# Mainboard_Encoder_Interface.net
KiCad netlist of a schematic drawn in Altium Designer
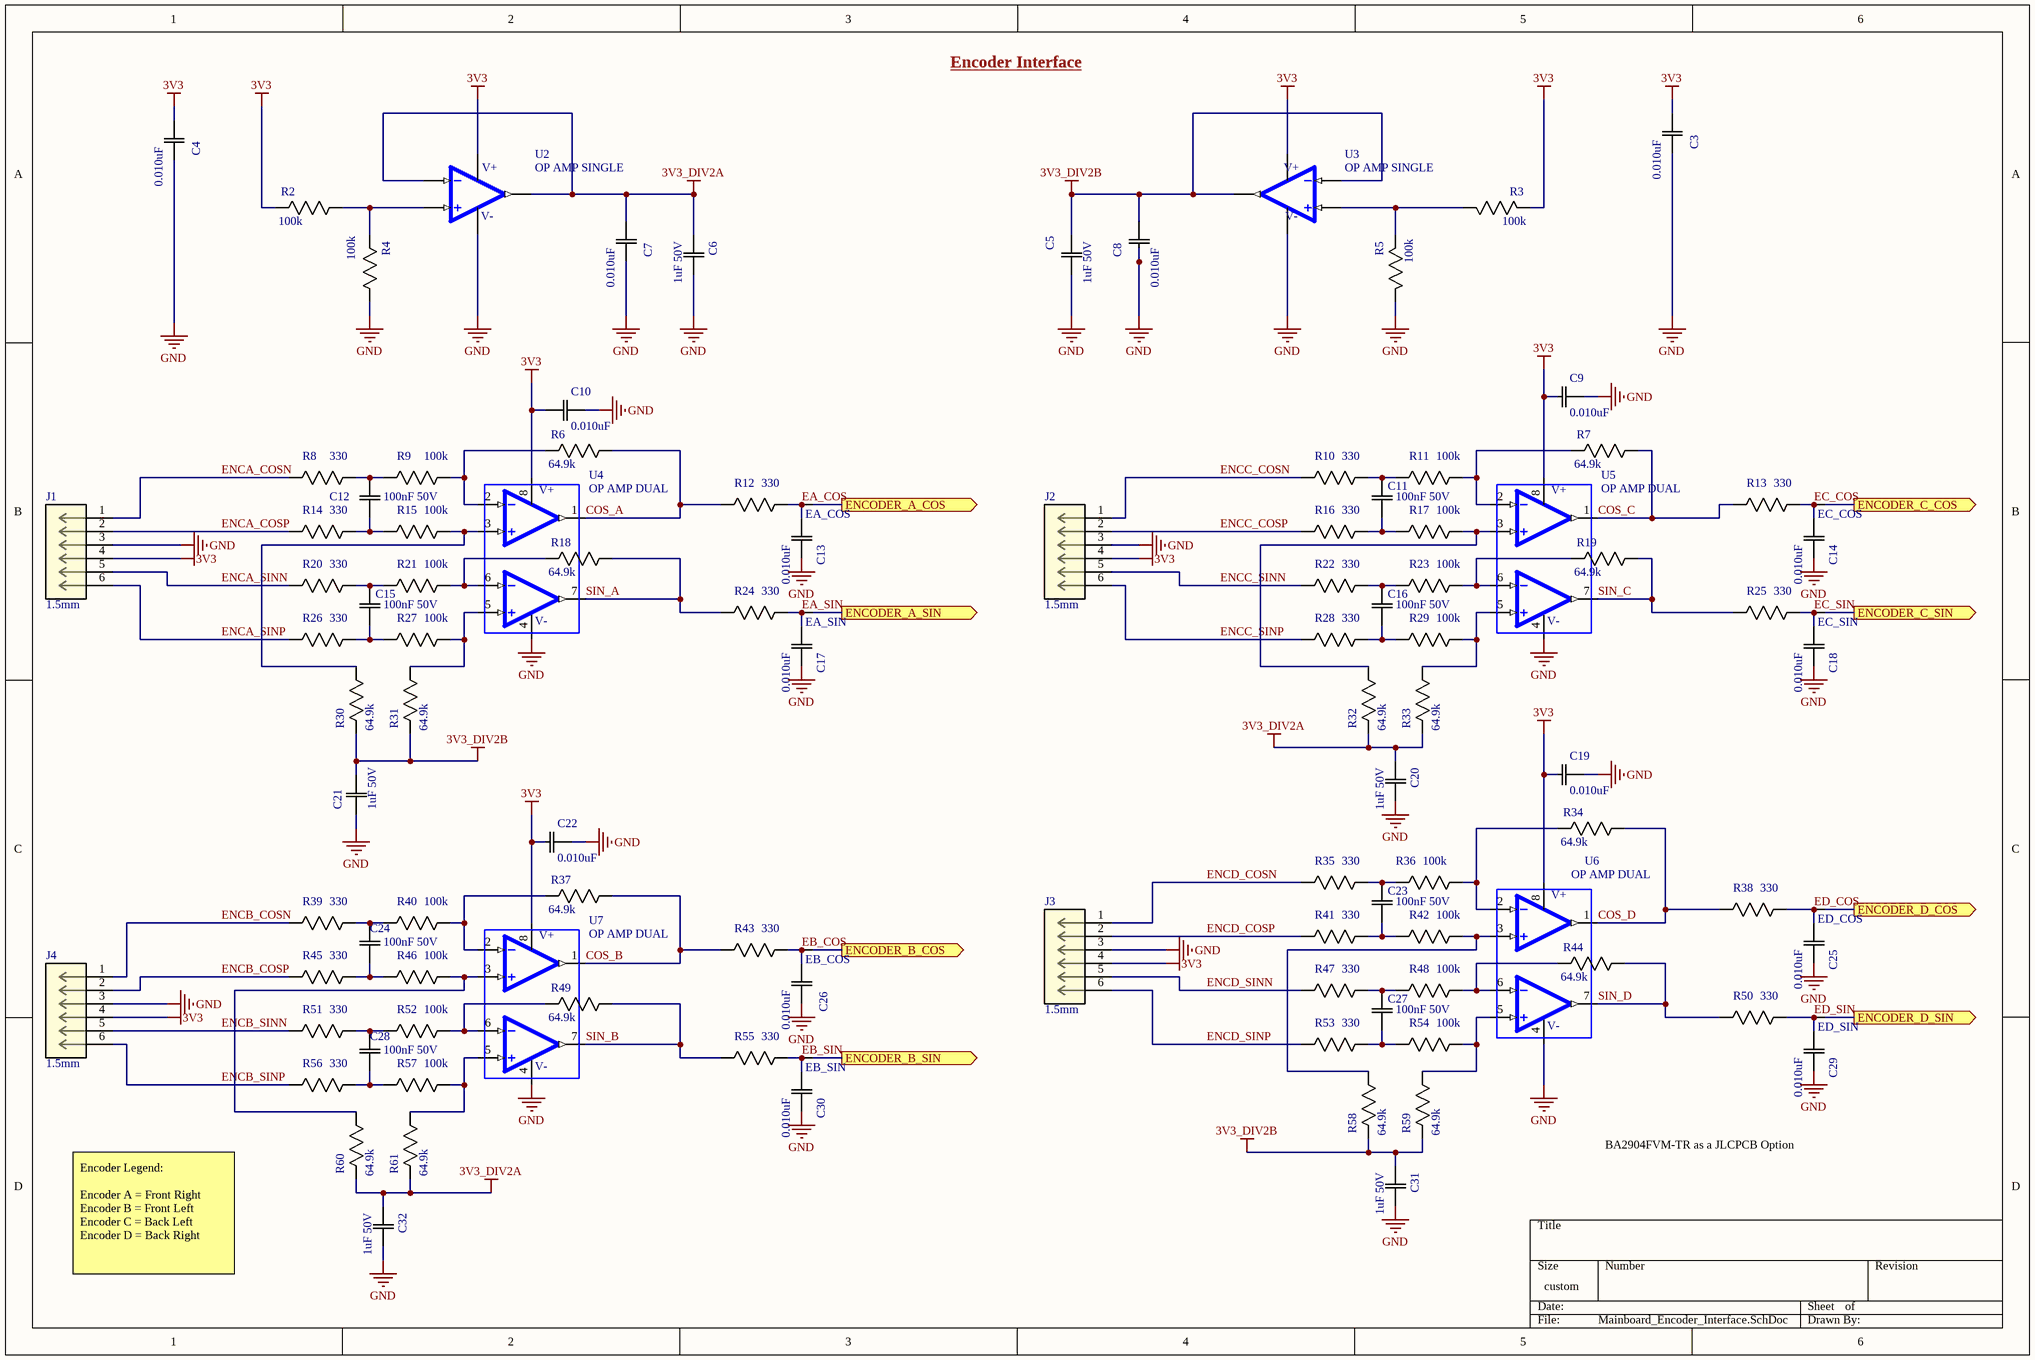
[diagram p0: Mainboard_Encoder_Interface.SchDoc]

(export (version "E")
  (design (tool "Eeschema 10.0.6"))
  (components
    (comp (ref "C3")
      (value "0.010uF")
      (footprint "0603")
      (description "CAP CER 0.010UF 50V X7R 0603/0805")
      (fields (field (name "TOLERANCE") "10%"))
      (libsource (lib "AltiumLibraries") (part "CAP 0.010uF 50V"))
    )
    (comp (ref "C4")
      (value "0.010uF")
      (footprint "0603")
      (description "CAP CER 0.010UF 50V X7R 0603/0805")
      (fields (field (name "TOLERANCE") "10%"))
      (libsource (lib "AltiumLibraries") (part "CAP 0.010uF 50V"))
    )
    (comp (ref "C5")
      (value "1uF 50V")
      (footprint "0603")
      (description "CAP CER 1UF 50V X7R 0805")
      (fields (field (name "TOLERANCE") "10%"))
      (libsource (lib "AltiumLibraries") (part "CAP 1uF 50V"))
    )
    (comp (ref "C6")
      (value "1uF 50V")
      (footprint "0603")
      (description "CAP CER 1UF 50V X7R 0805")
      (fields (field (name "TOLERANCE") "10%"))
      (libsource (lib "AltiumLibraries") (part "CAP 1uF 50V"))
    )
    (comp (ref "C7")
      (value "0.010uF")
      (footprint "0603")
      (description "CAP CER 0.010UF 50V X7R 0603/0805")
      (fields (field (name "TOLERANCE") "10%"))
      (libsource (lib "AltiumLibraries") (part "CAP 0.010uF 50V"))
    )
    (comp (ref "C8")
      (value "0.010uF")
      (footprint "0603")
      (description "CAP CER 0.010UF 50V X7R 0603/0805")
      (fields (field (name "TOLERANCE") "10%"))
      (libsource (lib "AltiumLibraries") (part "CAP 0.010uF 50V"))
    )
    (comp (ref "C9")
      (value "0.010uF")
      (footprint "0603")
      (description "CAP CER 0.010UF 50V X7R 0603/0805")
      (fields (field (name "TOLERANCE") "10%"))
      (libsource (lib "AltiumLibraries") (part "CAP 0.010uF 50V"))
    )
    (comp (ref "C10")
      (value "0.010uF")
      (footprint "0603")
      (description "CAP CER 0.010UF 50V X7R 0603/0805")
      (fields (field (name "TOLERANCE") "10%"))
      (libsource (lib "AltiumLibraries") (part "CAP 0.010uF 50V"))
    )
    (comp (ref "C11")
      (value "100nF 50V")
      (footprint "0603")
      (description "CAP CER 0.1UF 50V X7R 0805")
      (fields (field (name "TOLERANCE") "10%"))
      (libsource (lib "AltiumLibraries") (part "CAP 100nF 50V"))
    )
    (comp (ref "C12")
      (value "100nF 50V")
      (footprint "0603")
      (description "CAP CER 0.1UF 50V X7R 0805")
      (fields (field (name "TOLERANCE") "10%"))
      (libsource (lib "AltiumLibraries") (part "CAP 100nF 50V"))
    )
    (comp (ref "C13")
      (value "0.010uF")
      (footprint "0603")
      (description "CAP CER 0.010UF 50V X7R 0603/0805")
      (fields (field (name "TOLERANCE") "10%"))
      (libsource (lib "AltiumLibraries") (part "CAP 0.010uF 50V"))
    )
    (comp (ref "C14")
      (value "0.010uF")
      (footprint "0603")
      (description "CAP CER 0.010UF 50V X7R 0603/0805")
      (fields (field (name "TOLERANCE") "10%"))
      (libsource (lib "AltiumLibraries") (part "CAP 0.010uF 50V"))
    )
    (comp (ref "C15")
      (value "100nF 50V")
      (footprint "0603")
      (description "CAP CER 0.1UF 50V X7R 0805")
      (fields (field (name "TOLERANCE") "10%"))
      (libsource (lib "AltiumLibraries") (part "CAP 100nF 50V"))
    )
    (comp (ref "C16")
      (value "100nF 50V")
      (footprint "0603")
      (description "CAP CER 0.1UF 50V X7R 0805")
      (fields (field (name "TOLERANCE") "10%"))
      (libsource (lib "AltiumLibraries") (part "CAP 100nF 50V"))
    )
    (comp (ref "C17")
      (value "0.010uF")
      (footprint "0603")
      (description "CAP CER 0.010UF 50V X7R 0603/0805")
      (fields (field (name "TOLERANCE") "10%"))
      (libsource (lib "AltiumLibraries") (part "CAP 0.010uF 50V"))
    )
    (comp (ref "C18")
      (value "0.010uF")
      (footprint "0603")
      (description "CAP CER 0.010UF 50V X7R 0603/0805")
      (fields (field (name "TOLERANCE") "10%"))
      (libsource (lib "AltiumLibraries") (part "CAP 0.010uF 50V"))
    )
    (comp (ref "C19")
      (value "0.010uF")
      (footprint "0603")
      (description "CAP CER 0.010UF 50V X7R 0603/0805")
      (fields (field (name "TOLERANCE") "10%"))
      (libsource (lib "AltiumLibraries") (part "CAP 0.010uF 50V"))
    )
    (comp (ref "C20")
      (value "1uF 50V")
      (footprint "0603")
      (description "CAP CER 1UF 50V X7R 0805")
      (fields (field (name "TOLERANCE") "10%"))
      (libsource (lib "AltiumLibraries") (part "CAP 1uF 50V"))
    )
    (comp (ref "C21")
      (value "1uF 50V")
      (footprint "0603")
      (description "CAP CER 1UF 50V X7R 0805")
      (fields (field (name "TOLERANCE") "10%"))
      (libsource (lib "AltiumLibraries") (part "CAP 1uF 50V"))
    )
    (comp (ref "C22")
      (value "0.010uF")
      (footprint "0603")
      (description "CAP CER 0.010UF 50V X7R 0603/0805")
      (fields (field (name "TOLERANCE") "10%"))
      (libsource (lib "AltiumLibraries") (part "CAP 0.010uF 50V"))
    )
    (comp (ref "C23")
      (value "100nF 50V")
      (footprint "0603")
      (description "CAP CER 0.1UF 50V X7R 0805")
      (fields (field (name "TOLERANCE") "10%"))
      (libsource (lib "AltiumLibraries") (part "CAP 100nF 50V"))
    )
    (comp (ref "C24")
      (value "100nF 50V")
      (footprint "0603")
      (description "CAP CER 0.1UF 50V X7R 0805")
      (fields (field (name "TOLERANCE") "10%"))
      (libsource (lib "AltiumLibraries") (part "CAP 100nF 50V"))
    )
    (comp (ref "C25")
      (value "0.010uF")
      (footprint "0603")
      (description "CAP CER 0.010UF 50V X7R 0603/0805")
      (fields (field (name "TOLERANCE") "10%"))
      (libsource (lib "AltiumLibraries") (part "CAP 0.010uF 50V"))
    )
    (comp (ref "C26")
      (value "0.010uF")
      (footprint "0603")
      (description "CAP CER 0.010UF 50V X7R 0603/0805")
      (fields (field (name "TOLERANCE") "10%"))
      (libsource (lib "AltiumLibraries") (part "CAP 0.010uF 50V"))
    )
    (comp (ref "C27")
      (value "100nF 50V")
      (footprint "0603")
      (description "CAP CER 0.1UF 50V X7R 0805")
      (fields (field (name "TOLERANCE") "10%"))
      (libsource (lib "AltiumLibraries") (part "CAP 100nF 50V"))
    )
    (comp (ref "C28")
      (value "100nF 50V")
      (footprint "0603")
      (description "CAP CER 0.1UF 50V X7R 0805")
      (fields (field (name "TOLERANCE") "10%"))
      (libsource (lib "AltiumLibraries") (part "CAP 100nF 50V"))
    )
    (comp (ref "C29")
      (value "0.010uF")
      (footprint "0603")
      (description "CAP CER 0.010UF 50V X7R 0603/0805")
      (fields (field (name "TOLERANCE") "10%"))
      (libsource (lib "AltiumLibraries") (part "CAP 0.010uF 50V"))
    )
    (comp (ref "C30")
      (value "0.010uF")
      (footprint "0603")
      (description "CAP CER 0.010UF 50V X7R 0603/0805")
      (fields (field (name "TOLERANCE") "10%"))
      (libsource (lib "AltiumLibraries") (part "CAP 0.010uF 50V"))
    )
    (comp (ref "C31")
      (value "1uF 50V")
      (footprint "0603")
      (description "CAP CER 1UF 50V X7R 0805")
      (fields (field (name "TOLERANCE") "10%"))
      (libsource (lib "AltiumLibraries") (part "CAP 1uF 50V"))
    )
    (comp (ref "C32")
      (value "1uF 50V")
      (footprint "0603")
      (description "CAP CER 1UF 50V X7R 0805")
      (fields (field (name "TOLERANCE") "10%"))
      (libsource (lib "AltiumLibraries") (part "CAP 1uF 50V"))
    )
    (comp (ref "EA_COS")
      (value "Test Point (Via)")
      (footprint "TP")
      (libsource (lib "AltiumLibraries") (part "Test Point (Via)"))
    )
    (comp (ref "EA_SIN")
      (value "Test Point (Via)")
      (footprint "TP")
      (libsource (lib "AltiumLibraries") (part "Test Point (Via)"))
    )
    (comp (ref "EB_COS")
      (value "Test Point (Via)")
      (footprint "TP")
      (libsource (lib "AltiumLibraries") (part "Test Point (Via)"))
    )
    (comp (ref "EB_SIN")
      (value "Test Point (Via)")
      (footprint "TP")
      (libsource (lib "AltiumLibraries") (part "Test Point (Via)"))
    )
    (comp (ref "EC_COS")
      (value "Test Point (Via)")
      (footprint "TP")
      (libsource (lib "AltiumLibraries") (part "Test Point (Via)"))
    )
    (comp (ref "EC_SIN")
      (value "Test Point (Via)")
      (footprint "TP")
      (libsource (lib "AltiumLibraries") (part "Test Point (Via)"))
    )
    (comp (ref "ED_COS")
      (value "Test Point (Via)")
      (footprint "TP")
      (libsource (lib "AltiumLibraries") (part "Test Point (Via)"))
    )
    (comp (ref "ED_SIN")
      (value "Test Point (Via)")
      (footprint "TP")
      (libsource (lib "AltiumLibraries") (part "Test Point (Via)"))
    )
    (comp (ref "J1")
      (value "1.5mm")
      (footprint "6POS JST Vertical")
      (description "Conn Shrouded Header HDR 6 POS 1.5mm Solder RA Thru-Hole Box")
      (fields (field (name "MANUFACTURER") "JST") (field (name "MANUFACTURER PART NUMBER") "S6B-ZR(LF)(SN)"))
      (libsource (lib "AltiumLibraries") (part "CN 6POS JST RA"))
    )
    (comp (ref "J2")
      (value "1.5mm")
      (footprint "6POS JST Vertical")
      (description "Conn Shrouded Header HDR 6 POS 1.5mm Solder RA Thru-Hole Box")
      (fields (field (name "MANUFACTURER") "JST") (field (name "MANUFACTURER PART NUMBER") "S6B-ZR(LF)(SN)"))
      (libsource (lib "AltiumLibraries") (part "CN 6POS JST RA"))
    )
    (comp (ref "J3")
      (value "1.5mm")
      (footprint "6POS JST Vertical")
      (description "Conn Shrouded Header HDR 6 POS 1.5mm Solder RA Thru-Hole Box")
      (fields (field (name "MANUFACTURER") "JST") (field (name "MANUFACTURER PART NUMBER") "S6B-ZR(LF)(SN)"))
      (libsource (lib "AltiumLibraries") (part "CN 6POS JST RA"))
    )
    (comp (ref "J4")
      (value "1.5mm")
      (footprint "6POS JST Vertical")
      (description "Conn Shrouded Header HDR 6 POS 1.5mm Solder RA Thru-Hole Box")
      (fields (field (name "MANUFACTURER") "JST") (field (name "MANUFACTURER PART NUMBER") "S6B-ZR(LF)(SN)"))
      (libsource (lib "AltiumLibraries") (part "CN 6POS JST RA"))
    )
    (comp (ref "R2")
      (value "100k")
      (footprint "0603")
      (description "RES SMD 100K OHM 1% 1/8W 0805")
      (fields (field (name "TOLERANCE") "1%"))
      (libsource (lib "AltiumLibraries") (part "RES 100k 1/8W - 1%"))
    )
    (comp (ref "R3")
      (value "100k")
      (footprint "0603")
      (description "RES SMD 100K OHM 1% 1/8W 0805")
      (fields (field (name "TOLERANCE") "1%"))
      (libsource (lib "AltiumLibraries") (part "RES 100k 1/8W - 1%"))
    )
    (comp (ref "R4")
      (value "100k")
      (footprint "0603")
      (description "RES SMD 100K OHM 1% 1/8W 0805")
      (fields (field (name "TOLERANCE") "1%"))
      (libsource (lib "AltiumLibraries") (part "RES 100k 1/8W - 1%"))
    )
    (comp (ref "R5")
      (value "100k")
      (footprint "0603")
      (description "RES SMD 100K OHM 1% 1/8W 0805")
      (fields (field (name "TOLERANCE") "1%"))
      (libsource (lib "AltiumLibraries") (part "RES 100k 1/8W - 1%"))
    )
    (comp (ref "R6")
      (value "64.9k")
      (footprint "0603")
      (description "RES SMD 64.9K OHM 1% 1/8W 0805")
      (fields (field (name "TOLERANCE") "1%"))
      (libsource (lib "") (part "RES 64.9k 1/8W_1"))
    )
    (comp (ref "R7")
      (value "64.9k")
      (footprint "0603")
      (description "RES SMD 64.9K OHM 1% 1/8W 0805")
      (fields (field (name "TOLERANCE") "1%"))
      (libsource (lib "") (part "RES 64.9k 1/8W_1"))
    )
    (comp (ref "R8")
      (value "330")
      (footprint "0603")
      (description "RES SMD 330 OHM 1% 1/8W 0805")
      (fields (field (name "TOLERANCE") "1%"))
      (libsource (lib "") (part "RES 330.0 1/8W - 1%_1"))
    )
    (comp (ref "R9")
      (value "100k")
      (footprint "0603")
      (description "RES SMD 100K OHM 1% 1/8W 0805")
      (fields (field (name "TOLERANCE") "1%"))
      (libsource (lib "AltiumLibraries") (part "RES 100k 1/8W - 1%"))
    )
    (comp (ref "R10")
      (value "330")
      (footprint "0603")
      (description "RES SMD 330 OHM 1% 1/8W 0805")
      (fields (field (name "TOLERANCE") "1%"))
      (libsource (lib "") (part "RES 330.0 1/8W - 1%_1"))
    )
    (comp (ref "R11")
      (value "100k")
      (footprint "0603")
      (description "RES SMD 100K OHM 1% 1/8W 0805")
      (fields (field (name "TOLERANCE") "1%"))
      (libsource (lib "AltiumLibraries") (part "RES 100k 1/8W - 1%"))
    )
    (comp (ref "R12")
      (value "330")
      (footprint "0603")
      (description "RES SMD 330 OHM 1% 1/8W 0805")
      (fields (field (name "TOLERANCE") "1%"))
      (libsource (lib "AltiumLibraries") (part "RES 330.0 1/8W - 1%"))
    )
    (comp (ref "R13")
      (value "330")
      (footprint "0603")
      (description "RES SMD 330 OHM 1% 1/8W 0805")
      (fields (field (name "TOLERANCE") "1%"))
      (libsource (lib "AltiumLibraries") (part "RES 330.0 1/8W - 1%"))
    )
    (comp (ref "R14")
      (value "330")
      (footprint "0603")
      (description "RES SMD 330 OHM 1% 1/8W 0805")
      (fields (field (name "TOLERANCE") "1%"))
      (libsource (lib "") (part "RES 330.0 1/8W - 1%_1"))
    )
    (comp (ref "R15")
      (value "100k")
      (footprint "0603")
      (description "RES SMD 100K OHM 1% 1/8W 0805")
      (fields (field (name "TOLERANCE") "1%"))
      (libsource (lib "AltiumLibraries") (part "RES 100k 1/8W - 1%"))
    )
    (comp (ref "R16")
      (value "330")
      (footprint "0603")
      (description "RES SMD 330 OHM 1% 1/8W 0805")
      (fields (field (name "TOLERANCE") "1%"))
      (libsource (lib "") (part "RES 330.0 1/8W - 1%_1"))
    )
    (comp (ref "R17")
      (value "100k")
      (footprint "0603")
      (description "RES SMD 100K OHM 1% 1/8W 0805")
      (fields (field (name "TOLERANCE") "1%"))
      (libsource (lib "AltiumLibraries") (part "RES 100k 1/8W - 1%"))
    )
    (comp (ref "R18")
      (value "64.9k")
      (footprint "0603")
      (description "RES SMD 64.9K OHM 1% 1/8W 0805")
      (fields (field (name "TOLERANCE") "1%"))
      (libsource (lib "AltiumLibraries") (part "RES 64.9k 1/8W"))
    )
    (comp (ref "R19")
      (value "64.9k")
      (footprint "0603")
      (description "RES SMD 64.9K OHM 1% 1/8W 0805")
      (fields (field (name "TOLERANCE") "1%"))
      (libsource (lib "") (part "RES 64.9k 1/8W_1"))
    )
    (comp (ref "R20")
      (value "330")
      (footprint "0603")
      (description "RES SMD 330 OHM 1% 1/8W 0805")
      (fields (field (name "TOLERANCE") "1%"))
      (libsource (lib "") (part "RES 330.0 1/8W - 1%_1"))
    )
    (comp (ref "R21")
      (value "100k")
      (footprint "0603")
      (description "RES SMD 100K OHM 1% 1/8W 0805")
      (fields (field (name "TOLERANCE") "1%"))
      (libsource (lib "AltiumLibraries") (part "RES 100k 1/8W - 1%"))
    )
    (comp (ref "R22")
      (value "330")
      (footprint "0603")
      (description "RES SMD 330 OHM 1% 1/8W 0805")
      (fields (field (name "TOLERANCE") "1%"))
      (libsource (lib "") (part "RES 330.0 1/8W - 1%_1"))
    )
    (comp (ref "R23")
      (value "100k")
      (footprint "0603")
      (description "RES SMD 100K OHM 1% 1/8W 0805")
      (fields (field (name "TOLERANCE") "1%"))
      (libsource (lib "AltiumLibraries") (part "RES 100k 1/8W - 1%"))
    )
    (comp (ref "R24")
      (value "330")
      (footprint "0603")
      (description "RES SMD 330 OHM 1% 1/8W 0805")
      (fields (field (name "TOLERANCE") "1%"))
      (libsource (lib "") (part "RES 330.0 1/8W - 1%_1"))
    )
    (comp (ref "R25")
      (value "330")
      (footprint "0603")
      (description "RES SMD 330 OHM 1% 1/8W 0805")
      (fields (field (name "TOLERANCE") "1%"))
      (libsource (lib "AltiumLibraries") (part "RES 330.0 1/8W - 1%"))
    )
    (comp (ref "R26")
      (value "330")
      (footprint "0603")
      (description "RES SMD 330 OHM 1% 1/8W 0805")
      (fields (field (name "TOLERANCE") "1%"))
      (libsource (lib "") (part "RES 330.0 1/8W - 1%_1"))
    )
    (comp (ref "R27")
      (value "100k")
      (footprint "0603")
      (description "RES SMD 100K OHM 1% 1/8W 0805")
      (fields (field (name "TOLERANCE") "1%"))
      (libsource (lib "AltiumLibraries") (part "RES 100k 1/8W - 1%"))
    )
    (comp (ref "R28")
      (value "330")
      (footprint "0603")
      (description "RES SMD 330 OHM 1% 1/8W 0805")
      (fields (field (name "TOLERANCE") "1%"))
      (libsource (lib "") (part "RES 330.0 1/8W - 1%_1"))
    )
    (comp (ref "R29")
      (value "100k")
      (footprint "0603")
      (description "RES SMD 100K OHM 1% 1/8W 0805")
      (fields (field (name "TOLERANCE") "1%"))
      (libsource (lib "AltiumLibraries") (part "RES 100k 1/8W - 1%"))
    )
    (comp (ref "R30")
      (value "64.9k")
      (footprint "0603")
      (description "RES SMD 64.9K OHM 1% 1/8W 0805")
      (fields (field (name "TOLERANCE") "1%"))
      (libsource (lib "AltiumLibraries") (part "RES 64.9k 1/8W"))
    )
    (comp (ref "R31")
      (value "64.9k")
      (footprint "0603")
      (description "RES SMD 64.9K OHM 1% 1/8W 0805")
      (fields (field (name "TOLERANCE") "1%"))
      (libsource (lib "AltiumLibraries") (part "RES 64.9k 1/8W"))
    )
    (comp (ref "R32")
      (value "64.9k")
      (footprint "0603")
      (description "RES SMD 64.9K OHM 1% 1/8W 0805")
      (fields (field (name "TOLERANCE") "1%"))
      (libsource (lib "AltiumLibraries") (part "RES 64.9k 1/8W"))
    )
    (comp (ref "R33")
      (value "64.9k")
      (footprint "0603")
      (description "RES SMD 64.9K OHM 1% 1/8W 0805")
      (fields (field (name "TOLERANCE") "1%"))
      (libsource (lib "AltiumLibraries") (part "RES 64.9k 1/8W"))
    )
    (comp (ref "R34")
      (value "64.9k")
      (footprint "0603")
      (description "RES SMD 64.9K OHM 1% 1/8W 0805")
      (fields (field (name "TOLERANCE") "1%"))
      (libsource (lib "") (part "RES 64.9k 1/8W_1"))
    )
    (comp (ref "R35")
      (value "330")
      (footprint "0603")
      (description "RES SMD 330 OHM 1% 1/8W 0805")
      (fields (field (name "TOLERANCE") "1%"))
      (libsource (lib "") (part "RES 330.0 1/8W - 1%_1"))
    )
    (comp (ref "R36")
      (value "100k")
      (footprint "0603")
      (description "RES SMD 100K OHM 1% 1/8W 0805")
      (fields (field (name "TOLERANCE") "1%"))
      (libsource (lib "AltiumLibraries") (part "RES 100k 1/8W - 1%"))
    )
    (comp (ref "R37")
      (value "64.9k")
      (footprint "0603")
      (description "RES SMD 64.9K OHM 1% 1/8W 0805")
      (fields (field (name "TOLERANCE") "1%"))
      (libsource (lib "") (part "RES 64.9k 1/8W_1"))
    )
    (comp (ref "R38")
      (value "330")
      (footprint "0603")
      (description "RES SMD 330 OHM 1% 1/8W 0805")
      (fields (field (name "TOLERANCE") "1%"))
      (libsource (lib "") (part "RES 330.0 1/8W - 1%_1"))
    )
    (comp (ref "R39")
      (value "330")
      (footprint "0603")
      (description "RES SMD 330 OHM 1% 1/8W 0805")
      (fields (field (name "TOLERANCE") "1%"))
      (libsource (lib "") (part "RES 330.0 1/8W - 1%_1"))
    )
    (comp (ref "R40")
      (value "100k")
      (footprint "0603")
      (description "RES SMD 100K OHM 1% 1/8W 0805")
      (fields (field (name "TOLERANCE") "1%"))
      (libsource (lib "AltiumLibraries") (part "RES 100k 1/8W - 1%"))
    )
    (comp (ref "R41")
      (value "330")
      (footprint "0603")
      (description "RES SMD 330 OHM 1% 1/8W 0805")
      (fields (field (name "TOLERANCE") "1%"))
      (libsource (lib "") (part "RES 330.0 1/8W - 1%_1"))
    )
    (comp (ref "R42")
      (value "100k")
      (footprint "0603")
      (description "RES SMD 100K OHM 1% 1/8W 0805")
      (fields (field (name "TOLERANCE") "1%"))
      (libsource (lib "AltiumLibraries") (part "RES 100k 1/8W - 1%"))
    )
    (comp (ref "R43")
      (value "330")
      (footprint "0603")
      (description "RES SMD 330 OHM 1% 1/8W 0805")
      (fields (field (name "TOLERANCE") "1%"))
      (libsource (lib "AltiumLibraries") (part "RES 330.0 1/8W - 1%"))
    )
    (comp (ref "R44")
      (value "64.9k")
      (footprint "0603")
      (description "RES SMD 64.9K OHM 1% 1/8W 0805")
      (fields (field (name "TOLERANCE") "1%"))
      (libsource (lib "AltiumLibraries") (part "RES 64.9k 1/8W"))
    )
    (comp (ref "R45")
      (value "330")
      (footprint "0603")
      (description "RES SMD 330 OHM 1% 1/8W 0805")
      (fields (field (name "TOLERANCE") "1%"))
      (libsource (lib "") (part "RES 330.0 1/8W - 1%_1"))
    )
    (comp (ref "R46")
      (value "100k")
      (footprint "0603")
      (description "RES SMD 100K OHM 1% 1/8W 0805")
      (fields (field (name "TOLERANCE") "1%"))
      (libsource (lib "AltiumLibraries") (part "RES 100k 1/8W - 1%"))
    )
    (comp (ref "R47")
      (value "330")
      (footprint "0603")
      (description "RES SMD 330 OHM 1% 1/8W 0805")
      (fields (field (name "TOLERANCE") "1%"))
      (libsource (lib "") (part "RES 330.0 1/8W - 1%_1"))
    )
    (comp (ref "R48")
      (value "100k")
      (footprint "0603")
      (description "RES SMD 100K OHM 1% 1/8W 0805")
      (fields (field (name "TOLERANCE") "1%"))
      (libsource (lib "AltiumLibraries") (part "RES 100k 1/8W - 1%"))
    )
    (comp (ref "R49")
      (value "64.9k")
      (footprint "0603")
      (description "RES SMD 64.9K OHM 1% 1/8W 0805")
      (fields (field (name "TOLERANCE") "1%"))
      (libsource (lib "AltiumLibraries") (part "RES 64.9k 1/8W"))
    )
    (comp (ref "R50")
      (value "330")
      (footprint "0603")
      (description "RES SMD 330 OHM 1% 1/8W 0805")
      (fields (field (name "TOLERANCE") "1%"))
      (libsource (lib "") (part "RES 330.0 1/8W - 1%_1"))
    )
    (comp (ref "R51")
      (value "330")
      (footprint "0603")
      (description "RES SMD 330 OHM 1% 1/8W 0805")
      (fields (field (name "TOLERANCE") "1%"))
      (libsource (lib "") (part "RES 330.0 1/8W - 1%_1"))
    )
    (comp (ref "R52")
      (value "100k")
      (footprint "0603")
      (description "RES SMD 100K OHM 1% 1/8W 0805")
      (fields (field (name "TOLERANCE") "1%"))
      (libsource (lib "AltiumLibraries") (part "RES 100k 1/8W - 1%"))
    )
    (comp (ref "R53")
      (value "330")
      (footprint "0603")
      (description "RES SMD 330 OHM 1% 1/8W 0805")
      (fields (field (name "TOLERANCE") "1%"))
      (libsource (lib "") (part "RES 330.0 1/8W - 1%_1"))
    )
    (comp (ref "R54")
      (value "100k")
      (footprint "0603")
      (description "RES SMD 100K OHM 1% 1/8W 0805")
      (fields (field (name "TOLERANCE") "1%"))
      (libsource (lib "AltiumLibraries") (part "RES 100k 1/8W - 1%"))
    )
    (comp (ref "R55")
      (value "330")
      (footprint "0603")
      (description "RES SMD 330 OHM 1% 1/8W 0805")
      (fields (field (name "TOLERANCE") "1%"))
      (libsource (lib "AltiumLibraries") (part "RES 330.0 1/8W - 1%"))
    )
    (comp (ref "R56")
      (value "330")
      (footprint "0603")
      (description "RES SMD 330 OHM 1% 1/8W 0805")
      (fields (field (name "TOLERANCE") "1%"))
      (libsource (lib "") (part "RES 330.0 1/8W - 1%_1"))
    )
    (comp (ref "R57")
      (value "100k")
      (footprint "0603")
      (description "RES SMD 100K OHM 1% 1/8W 0805")
      (fields (field (name "TOLERANCE") "1%"))
      (libsource (lib "AltiumLibraries") (part "RES 100k 1/8W - 1%"))
    )
    (comp (ref "R58")
      (value "64.9k")
      (footprint "0603")
      (description "RES SMD 64.9K OHM 1% 1/8W 0805")
      (fields (field (name "TOLERANCE") "1%"))
      (libsource (lib "AltiumLibraries") (part "RES 64.9k 1/8W"))
    )
    (comp (ref "R59")
      (value "64.9k")
      (footprint "0603")
      (description "RES SMD 64.9K OHM 1% 1/8W 0805")
      (fields (field (name "TOLERANCE") "1%"))
      (libsource (lib "AltiumLibraries") (part "RES 64.9k 1/8W"))
    )
    (comp (ref "R60")
      (value "64.9k")
      (footprint "0603")
      (description "RES SMD 64.9K OHM 1% 1/8W 0805")
      (fields (field (name "TOLERANCE") "1%"))
      (libsource (lib "AltiumLibraries") (part "RES 64.9k 1/8W"))
    )
    (comp (ref "R61")
      (value "64.9k")
      (footprint "0603")
      (description "RES SMD 64.9K OHM 1% 1/8W 0805")
      (fields (field (name "TOLERANCE") "1%"))
      (libsource (lib "AltiumLibraries") (part "RES 64.9k 1/8W"))
    )
    (comp (ref "U2")
      (value "OP AMP SINGLE")
      (footprint "SOT95P280X145-5N")
      (description "ANALOG DEVICES - ADA4505-1ARJZ-R7 - IC, AMPLIF. OPER., R-R, CMOS, SOT23-5")
      (fields
        (field (name "MANUFACTURER") "Analog Devices")
        (field (name "MANUFACTURER PART NUMBER") "ADA4505-1ARJZ-R7")
      )
      (libsource (lib "AltiumLibraries") (part "OP AMP SINGLE"))
    )
    (comp (ref "U3")
      (value "OP AMP SINGLE")
      (footprint "SOT95P280X145-5N")
      (description "ANALOG DEVICES - ADA4505-1ARJZ-R7 - IC, AMPLIF. OPER., R-R, CMOS, SOT23-5")
      (fields
        (field (name "MANUFACTURER") "Analog Devices")
        (field (name "MANUFACTURER PART NUMBER") "ADA4505-1ARJZ-R7")
      )
      (libsource (lib "AltiumLibraries") (part "OP AMP SINGLE"))
    )
    (comp (ref "U4")
      (value "OP AMP DUAL")
      (footprint "8-MSOP")
      (description "IC OPAMP VFB 50KHZ RRO 8MSOP")
      (fields
        (field (name "MANUFACTURER") "Analog Devices")
        (field (name "MANUFACTURER PART NUMBER") "ADA4505-2ARMZ")
      )
      (libsource (lib "AltiumLibraries") (part "OP AMP DUAL"))
    )
    (comp (ref "U5")
      (value "OP AMP DUAL")
      (footprint "8-MSOP")
      (description "IC OPAMP VFB 50KHZ RRO 8MSOP")
      (fields
        (field (name "MANUFACTURER") "Analog Devices")
        (field (name "MANUFACTURER PART NUMBER") "ADA4505-2ARMZ")
      )
      (libsource (lib "AltiumLibraries") (part "OP AMP DUAL"))
    )
    (comp (ref "U6")
      (value "OP AMP DUAL")
      (footprint "8-MSOP")
      (description "IC OPAMP VFB 50KHZ RRO 8MSOP")
      (fields
        (field (name "MANUFACTURER") "Analog Devices")
        (field (name "MANUFACTURER PART NUMBER") "ADA4505-2ARMZ")
      )
      (libsource (lib "AltiumLibraries") (part "OP AMP DUAL"))
    )
    (comp (ref "U7")
      (value "OP AMP DUAL")
      (footprint "8-MSOP")
      (description "IC OPAMP VFB 50KHZ RRO 8MSOP")
      (fields
        (field (name "MANUFACTURER") "Analog Devices")
        (field (name "MANUFACTURER PART NUMBER") "ADA4505-2ARMZ")
      )
      (libsource (lib "AltiumLibraries") (part "OP AMP DUAL"))
    )
  )
  (nets
    (net (code "1") (name "/COS_A") (class "Default")
      (node (ref "R12") (pin "2") (pinfunction "R2_2") (pintype "passive"))
      (node (ref "R6") (pin "1") (pinfunction "R1_1") (pintype "passive"))
      (node (ref "U4") (pin "1") (pinfunction "OUTA_1") (pintype "output"))
    )
    (net (code "2") (name "/COS_B") (class "Default")
      (node (ref "R37") (pin "1") (pinfunction "R1_1") (pintype "passive"))
      (node (ref "R43") (pin "2") (pinfunction "R2_2") (pintype "passive"))
      (node (ref "U7") (pin "1") (pinfunction "OUTA_1") (pintype "output"))
    )
    (net (code "3") (name "/COS_C") (class "Default")
      (node (ref "R13") (pin "2") (pinfunction "R2_2") (pintype "passive"))
      (node (ref "R7") (pin "1") (pinfunction "R1_1") (pintype "passive"))
      (node (ref "U5") (pin "1") (pinfunction "OUTA_1") (pintype "output"))
    )
    (net (code "4") (name "/COS_D") (class "Default")
      (node (ref "R34") (pin "1") (pinfunction "R1_1") (pintype "passive"))
      (node (ref "R38") (pin "2") (pinfunction "R2_2") (pintype "passive"))
      (node (ref "U6") (pin "1") (pinfunction "OUTA_1") (pintype "output"))
    )
    (net (code "5") (name "/EA_COS") (class "Default")
      (node (ref "C13") (pin "1") (pinfunction "C1_1") (pintype "passive"))
      (node (ref "EA_COS") (pin "1") (pinfunction "1_1") (pintype "passive"))
      (node (ref "R12") (pin "1") (pinfunction "R1_1") (pintype "passive"))
    )
    (net (code "6") (name "/EA_SIN") (class "Default")
      (node (ref "C17") (pin "1") (pinfunction "C1_1") (pintype "passive"))
      (node (ref "EA_SIN") (pin "1") (pinfunction "1_1") (pintype "passive"))
      (node (ref "R24") (pin "1") (pinfunction "R1_1") (pintype "passive"))
    )
    (net (code "7") (name "/EB_COS") (class "Default")
      (node (ref "C26") (pin "1") (pinfunction "C1_1") (pintype "passive"))
      (node (ref "EB_COS") (pin "1") (pinfunction "1_1") (pintype "passive"))
      (node (ref "R43") (pin "1") (pinfunction "R1_1") (pintype "passive"))
    )
    (net (code "8") (name "/EB_SIN") (class "Default")
      (node (ref "C30") (pin "1") (pinfunction "C1_1") (pintype "passive"))
      (node (ref "EB_SIN") (pin "1") (pinfunction "1_1") (pintype "passive"))
      (node (ref "R55") (pin "1") (pinfunction "R1_1") (pintype "passive"))
    )
    (net (code "9") (name "/EC_COS") (class "Default")
      (node (ref "C14") (pin "1") (pinfunction "C1_1") (pintype "passive"))
      (node (ref "EC_COS") (pin "1") (pinfunction "1_1") (pintype "passive"))
      (node (ref "R13") (pin "1") (pinfunction "R1_1") (pintype "passive"))
    )
    (net (code "10") (name "/EC_SIN") (class "Default")
      (node (ref "C18") (pin "1") (pinfunction "C1_1") (pintype "passive"))
      (node (ref "EC_SIN") (pin "1") (pinfunction "1_1") (pintype "passive"))
      (node (ref "R25") (pin "1") (pinfunction "R1_1") (pintype "passive"))
    )
    (net (code "11") (name "/ED_COS") (class "Default")
      (node (ref "C25") (pin "1") (pinfunction "C1_1") (pintype "passive"))
      (node (ref "ED_COS") (pin "1") (pinfunction "1_1") (pintype "passive"))
      (node (ref "R38") (pin "1") (pinfunction "R1_1") (pintype "passive"))
    )
    (net (code "12") (name "/ED_SIN") (class "Default")
      (node (ref "C29") (pin "1") (pinfunction "C1_1") (pintype "passive"))
      (node (ref "ED_SIN") (pin "1") (pinfunction "1_1") (pintype "passive"))
      (node (ref "R50") (pin "1") (pinfunction "R1_1") (pintype "passive"))
    )
    (net (code "13") (name "/ENCA_COSN") (class "Default")
      (node (ref "J1") (pin "1") (pinfunction "1_1") (pintype "passive"))
      (node (ref "R8") (pin "2") (pinfunction "R2_2") (pintype "passive"))
    )
    (net (code "14") (name "/ENCA_COSP") (class "Default")
      (node (ref "J1") (pin "2") (pinfunction "2_2") (pintype "passive"))
      (node (ref "R14") (pin "2") (pinfunction "R2_2") (pintype "passive"))
    )
    (net (code "15") (name "/ENCA_SINN") (class "Default")
      (node (ref "J1") (pin "5") (pinfunction "5_5") (pintype "passive"))
      (node (ref "R20") (pin "2") (pinfunction "R2_2") (pintype "passive"))
    )
    (net (code "16") (name "/ENCA_SINP") (class "Default")
      (node (ref "J1") (pin "6") (pinfunction "6_6") (pintype "passive"))
      (node (ref "R26") (pin "2") (pinfunction "R2_2") (pintype "passive"))
    )
    (net (code "17") (name "/ENCB_COSN") (class "Default")
      (node (ref "J4") (pin "1") (pinfunction "1_1") (pintype "passive"))
      (node (ref "R39") (pin "2") (pinfunction "R2_2") (pintype "passive"))
    )
    (net (code "18") (name "/ENCB_COSP") (class "Default")
      (node (ref "J4") (pin "2") (pinfunction "2_2") (pintype "passive"))
      (node (ref "R45") (pin "2") (pinfunction "R2_2") (pintype "passive"))
    )
    (net (code "19") (name "/ENCB_SINN") (class "Default")
      (node (ref "J4") (pin "5") (pinfunction "5_5") (pintype "passive"))
      (node (ref "R51") (pin "2") (pinfunction "R2_2") (pintype "passive"))
    )
    (net (code "20") (name "/ENCB_SINP") (class "Default")
      (node (ref "J4") (pin "6") (pinfunction "6_6") (pintype "passive"))
      (node (ref "R56") (pin "2") (pinfunction "R2_2") (pintype "passive"))
    )
    (net (code "21") (name "/ENCC_COSN") (class "Default")
      (node (ref "J2") (pin "1") (pinfunction "1_1") (pintype "passive"))
      (node (ref "R10") (pin "2") (pinfunction "R2_2") (pintype "passive"))
    )
    (net (code "22") (name "/ENCC_COSP") (class "Default")
      (node (ref "J2") (pin "2") (pinfunction "2_2") (pintype "passive"))
      (node (ref "R16") (pin "2") (pinfunction "R2_2") (pintype "passive"))
    )
    (net (code "23") (name "/ENCC_SINN") (class "Default")
      (node (ref "J2") (pin "5") (pinfunction "5_5") (pintype "passive"))
      (node (ref "R22") (pin "2") (pinfunction "R2_2") (pintype "passive"))
    )
    (net (code "24") (name "/ENCC_SINP") (class "Default")
      (node (ref "J2") (pin "6") (pinfunction "6_6") (pintype "passive"))
      (node (ref "R28") (pin "2") (pinfunction "R2_2") (pintype "passive"))
    )
    (net (code "25") (name "/ENCD_COSN") (class "Default")
      (node (ref "J3") (pin "1") (pinfunction "1_1") (pintype "passive"))
      (node (ref "R35") (pin "2") (pinfunction "R2_2") (pintype "passive"))
    )
    (net (code "26") (name "/ENCD_COSP") (class "Default")
      (node (ref "J3") (pin "2") (pinfunction "2_2") (pintype "passive"))
      (node (ref "R41") (pin "2") (pinfunction "R2_2") (pintype "passive"))
    )
    (net (code "27") (name "/ENCD_SINN") (class "Default")
      (node (ref "J3") (pin "5") (pinfunction "5_5") (pintype "passive"))
      (node (ref "R47") (pin "2") (pinfunction "R2_2") (pintype "passive"))
    )
    (net (code "28") (name "/ENCD_SINP") (class "Default")
      (node (ref "J3") (pin "6") (pinfunction "6_6") (pintype "passive"))
      (node (ref "R53") (pin "2") (pinfunction "R2_2") (pintype "passive"))
    )
    (net (code "29") (name "/SIN_A") (class "Default")
      (node (ref "R18") (pin "1") (pinfunction "R1_1") (pintype "passive"))
      (node (ref "R24") (pin "2") (pinfunction "R2_2") (pintype "passive"))
      (node (ref "U4") (pin "7") (pinfunction "OUTB_7") (pintype "output"))
    )
    (net (code "30") (name "/SIN_B") (class "Default")
      (node (ref "R49") (pin "1") (pinfunction "R1_1") (pintype "passive"))
      (node (ref "R55") (pin "2") (pinfunction "R2_2") (pintype "passive"))
      (node (ref "U7") (pin "7") (pinfunction "OUTB_7") (pintype "output"))
    )
    (net (code "31") (name "/SIN_C") (class "Default")
      (node (ref "R19") (pin "1") (pinfunction "R1_1") (pintype "passive"))
      (node (ref "R25") (pin "2") (pinfunction "R2_2") (pintype "passive"))
      (node (ref "U5") (pin "7") (pinfunction "OUTB_7") (pintype "output"))
    )
    (net (code "32") (name "/SIN_D") (class "Default")
      (node (ref "R44") (pin "1") (pinfunction "R1_1") (pintype "passive"))
      (node (ref "R50") (pin "2") (pinfunction "R2_2") (pintype "passive"))
      (node (ref "U6") (pin "7") (pinfunction "OUTB_7") (pintype "output"))
    )
    (net (code "33") (name "3V3") (class "Default")
      (node (ref "C10") (pin "1") (pinfunction "C1_1") (pintype "passive"))
      (node (ref "C19") (pin "1") (pinfunction "C1_1") (pintype "passive"))
      (node (ref "C22") (pin "1") (pinfunction "C1_1") (pintype "passive"))
      (node (ref "C3") (pin "1") (pinfunction "C1_1") (pintype "passive"))
      (node (ref "C4") (pin "1") (pinfunction "C1_1") (pintype "passive"))
      (node (ref "C9") (pin "1") (pinfunction "C1_1") (pintype "passive"))
      (node (ref "J1") (pin "4") (pinfunction "4_4") (pintype "passive"))
      (node (ref "J2") (pin "4") (pinfunction "4_4") (pintype "passive"))
      (node (ref "J3") (pin "4") (pinfunction "4_4") (pintype "passive"))
      (node (ref "J4") (pin "4") (pinfunction "4_4") (pintype "passive"))
      (node (ref "R2") (pin "2") (pinfunction "R2_2") (pintype "passive"))
      (node (ref "R3") (pin "2") (pinfunction "R2_2") (pintype "passive"))
      (node (ref "U2") (pin "5") (pinfunction "V+_5") (pintype "power_in"))
      (node (ref "U3") (pin "5") (pinfunction "V+_5") (pintype "power_in"))
      (node (ref "U4") (pin "8") (pinfunction "V+_8") (pintype "power_in"))
      (node (ref "U5") (pin "8") (pinfunction "V+_8") (pintype "power_in"))
      (node (ref "U6") (pin "8") (pinfunction "V+_8") (pintype "power_in"))
      (node (ref "U7") (pin "8") (pinfunction "V+_8") (pintype "power_in"))
    )
    (net (code "34") (name "3V3_DIV2A") (class "Default")
      (node (ref "C20") (pin "1") (pinfunction "C1_1") (pintype "passive"))
      (node (ref "C32") (pin "1") (pinfunction "C1_1") (pintype "passive"))
      (node (ref "C6") (pin "1") (pinfunction "C1_1") (pintype "passive"))
      (node (ref "C7") (pin "1") (pinfunction "C1_1") (pintype "passive"))
      (node (ref "R32") (pin "2") (pinfunction "R2_2") (pintype "passive"))
      (node (ref "R33") (pin "2") (pinfunction "R2_2") (pintype "passive"))
      (node (ref "R60") (pin "2") (pinfunction "R2_2") (pintype "passive"))
      (node (ref "R61") (pin "2") (pinfunction "R2_2") (pintype "passive"))
      (node (ref "U2") (pin "1") (pinfunction "OUT_1") (pintype "output"))
      (node (ref "U2") (pin "4") (pinfunction "IN-_4") (pintype "input"))
    )
    (net (code "35") (name "3V3_DIV2B") (class "Default")
      (node (ref "C21") (pin "2") (pinfunction "C2_2") (pintype "passive"))
      (node (ref "C31") (pin "1") (pinfunction "C1_1") (pintype "passive"))
      (node (ref "C5") (pin "1") (pinfunction "C1_1") (pintype "passive"))
      (node (ref "C8") (pin "1") (pinfunction "C1_1") (pintype "passive"))
      (node (ref "R30") (pin "2") (pinfunction "R2_2") (pintype "passive"))
      (node (ref "R31") (pin "2") (pinfunction "R2_2") (pintype "passive"))
      (node (ref "R58") (pin "2") (pinfunction "R2_2") (pintype "passive"))
      (node (ref "R59") (pin "2") (pinfunction "R2_2") (pintype "passive"))
      (node (ref "U3") (pin "1") (pinfunction "OUT_1") (pintype "output"))
      (node (ref "U3") (pin "4") (pinfunction "IN-_4") (pintype "input"))
    )
    (net (code "36") (name "GND") (class "Default")
      (node (ref "C10") (pin "2") (pinfunction "C2_2") (pintype "passive"))
      (node (ref "C13") (pin "2") (pinfunction "C2_2") (pintype "passive"))
      (node (ref "C14") (pin "2") (pinfunction "C2_2") (pintype "passive"))
      (node (ref "C17") (pin "2") (pinfunction "C2_2") (pintype "passive"))
      (node (ref "C18") (pin "2") (pinfunction "C2_2") (pintype "passive"))
      (node (ref "C19") (pin "2") (pinfunction "C2_2") (pintype "passive"))
      (node (ref "C20") (pin "2") (pinfunction "C2_2") (pintype "passive"))
      (node (ref "C21") (pin "1") (pinfunction "C1_1") (pintype "passive"))
      (node (ref "C22") (pin "2") (pinfunction "C2_2") (pintype "passive"))
      (node (ref "C25") (pin "2") (pinfunction "C2_2") (pintype "passive"))
      (node (ref "C26") (pin "2") (pinfunction "C2_2") (pintype "passive"))
      (node (ref "C29") (pin "2") (pinfunction "C2_2") (pintype "passive"))
      (node (ref "C3") (pin "2") (pinfunction "C2_2") (pintype "passive"))
      (node (ref "C30") (pin "2") (pinfunction "C2_2") (pintype "passive"))
      (node (ref "C31") (pin "2") (pinfunction "C2_2") (pintype "passive"))
      (node (ref "C32") (pin "2") (pinfunction "C2_2") (pintype "passive"))
      (node (ref "C4") (pin "2") (pinfunction "C2_2") (pintype "passive"))
      (node (ref "C5") (pin "2") (pinfunction "C2_2") (pintype "passive"))
      (node (ref "C6") (pin "2") (pinfunction "C2_2") (pintype "passive"))
      (node (ref "C7") (pin "2") (pinfunction "C2_2") (pintype "passive"))
      (node (ref "C8") (pin "2") (pinfunction "C2_2") (pintype "passive"))
      (node (ref "C9") (pin "2") (pinfunction "C2_2") (pintype "passive"))
      (node (ref "J1") (pin "3") (pinfunction "3_3") (pintype "passive"))
      (node (ref "J2") (pin "3") (pinfunction "3_3") (pintype "passive"))
      (node (ref "J3") (pin "3") (pinfunction "3_3") (pintype "passive"))
      (node (ref "J4") (pin "3") (pinfunction "3_3") (pintype "passive"))
      (node (ref "R4") (pin "1") (pinfunction "R1_1") (pintype "passive"))
      (node (ref "R5") (pin "1") (pinfunction "R1_1") (pintype "passive"))
      (node (ref "U2") (pin "2") (pinfunction "V-_2") (pintype "power_in"))
      (node (ref "U3") (pin "2") (pinfunction "V-_2") (pintype "power_in"))
      (node (ref "U4") (pin "4") (pinfunction "V-_4") (pintype "power_in"))
      (node (ref "U5") (pin "4") (pinfunction "V-_4") (pintype "power_in"))
      (node (ref "U6") (pin "4") (pinfunction "V-_4") (pintype "power_in"))
      (node (ref "U7") (pin "4") (pinfunction "V-_4") (pintype "power_in"))
    )
    (net (code "37") (name "Net-(C11-C1)") (class "Default")
      (node (ref "C11") (pin "1") (pinfunction "C1_1") (pintype "passive"))
      (node (ref "R10") (pin "1") (pinfunction "R1_1") (pintype "passive"))
      (node (ref "R11") (pin "2") (pinfunction "R2_2") (pintype "passive"))
    )
    (net (code "38") (name "Net-(C11-C2)") (class "Default")
      (node (ref "C11") (pin "2") (pinfunction "C2_2") (pintype "passive"))
      (node (ref "R16") (pin "1") (pinfunction "R1_1") (pintype "passive"))
      (node (ref "R17") (pin "2") (pinfunction "R2_2") (pintype "passive"))
    )
    (net (code "39") (name "Net-(C12-C1)") (class "Default")
      (node (ref "C12") (pin "1") (pinfunction "C1_1") (pintype "passive"))
      (node (ref "R8") (pin "1") (pinfunction "R1_1") (pintype "passive"))
      (node (ref "R9") (pin "2") (pinfunction "R2_2") (pintype "passive"))
    )
    (net (code "40") (name "Net-(C12-C2)") (class "Default")
      (node (ref "C12") (pin "2") (pinfunction "C2_2") (pintype "passive"))
      (node (ref "R14") (pin "1") (pinfunction "R1_1") (pintype "passive"))
      (node (ref "R15") (pin "2") (pinfunction "R2_2") (pintype "passive"))
    )
    (net (code "41") (name "Net-(C15-C1)") (class "Default")
      (node (ref "C15") (pin "1") (pinfunction "C1_1") (pintype "passive"))
      (node (ref "R20") (pin "1") (pinfunction "R1_1") (pintype "passive"))
      (node (ref "R21") (pin "2") (pinfunction "R2_2") (pintype "passive"))
    )
    (net (code "42") (name "Net-(C15-C2)") (class "Default")
      (node (ref "C15") (pin "2") (pinfunction "C2_2") (pintype "passive"))
      (node (ref "R26") (pin "1") (pinfunction "R1_1") (pintype "passive"))
      (node (ref "R27") (pin "2") (pinfunction "R2_2") (pintype "passive"))
    )
    (net (code "43") (name "Net-(C16-C1)") (class "Default")
      (node (ref "C16") (pin "1") (pinfunction "C1_1") (pintype "passive"))
      (node (ref "R22") (pin "1") (pinfunction "R1_1") (pintype "passive"))
      (node (ref "R23") (pin "2") (pinfunction "R2_2") (pintype "passive"))
    )
    (net (code "44") (name "Net-(C16-C2)") (class "Default")
      (node (ref "C16") (pin "2") (pinfunction "C2_2") (pintype "passive"))
      (node (ref "R28") (pin "1") (pinfunction "R1_1") (pintype "passive"))
      (node (ref "R29") (pin "2") (pinfunction "R2_2") (pintype "passive"))
    )
    (net (code "45") (name "Net-(C23-C1)") (class "Default")
      (node (ref "C23") (pin "1") (pinfunction "C1_1") (pintype "passive"))
      (node (ref "R35") (pin "1") (pinfunction "R1_1") (pintype "passive"))
      (node (ref "R36") (pin "2") (pinfunction "R2_2") (pintype "passive"))
    )
    (net (code "46") (name "Net-(C23-C2)") (class "Default")
      (node (ref "C23") (pin "2") (pinfunction "C2_2") (pintype "passive"))
      (node (ref "R41") (pin "1") (pinfunction "R1_1") (pintype "passive"))
      (node (ref "R42") (pin "2") (pinfunction "R2_2") (pintype "passive"))
    )
    (net (code "47") (name "Net-(C24-C1)") (class "Default")
      (node (ref "C24") (pin "1") (pinfunction "C1_1") (pintype "passive"))
      (node (ref "R39") (pin "1") (pinfunction "R1_1") (pintype "passive"))
      (node (ref "R40") (pin "2") (pinfunction "R2_2") (pintype "passive"))
    )
    (net (code "48") (name "Net-(C24-C2)") (class "Default")
      (node (ref "C24") (pin "2") (pinfunction "C2_2") (pintype "passive"))
      (node (ref "R45") (pin "1") (pinfunction "R1_1") (pintype "passive"))
      (node (ref "R46") (pin "2") (pinfunction "R2_2") (pintype "passive"))
    )
    (net (code "49") (name "Net-(C27-C1)") (class "Default")
      (node (ref "C27") (pin "1") (pinfunction "C1_1") (pintype "passive"))
      (node (ref "R47") (pin "1") (pinfunction "R1_1") (pintype "passive"))
      (node (ref "R48") (pin "2") (pinfunction "R2_2") (pintype "passive"))
    )
    (net (code "50") (name "Net-(C27-C2)") (class "Default")
      (node (ref "C27") (pin "2") (pinfunction "C2_2") (pintype "passive"))
      (node (ref "R53") (pin "1") (pinfunction "R1_1") (pintype "passive"))
      (node (ref "R54") (pin "2") (pinfunction "R2_2") (pintype "passive"))
    )
    (net (code "51") (name "Net-(C28-C1)") (class "Default")
      (node (ref "C28") (pin "1") (pinfunction "C1_1") (pintype "passive"))
      (node (ref "R51") (pin "1") (pinfunction "R1_1") (pintype "passive"))
      (node (ref "R52") (pin "2") (pinfunction "R2_2") (pintype "passive"))
    )
    (net (code "52") (name "Net-(C28-C2)") (class "Default")
      (node (ref "C28") (pin "2") (pinfunction "C2_2") (pintype "passive"))
      (node (ref "R56") (pin "1") (pinfunction "R1_1") (pintype "passive"))
      (node (ref "R57") (pin "2") (pinfunction "R2_2") (pintype "passive"))
    )
    (net (code "53") (name "Net-(R2-R1)") (class "Default")
      (node (ref "R2") (pin "1") (pinfunction "R1_1") (pintype "passive"))
      (node (ref "R4") (pin "2") (pinfunction "R2_2") (pintype "passive"))
      (node (ref "U2") (pin "3") (pinfunction "IN+_3") (pintype "input"))
    )
    (net (code "54") (name "Net-(R3-R1)") (class "Default")
      (node (ref "R3") (pin "1") (pinfunction "R1_1") (pintype "passive"))
      (node (ref "R5") (pin "2") (pinfunction "R2_2") (pintype "passive"))
      (node (ref "U3") (pin "3") (pinfunction "IN+_3") (pintype "input"))
    )
    (net (code "55") (name "Net-(R6-R2)") (class "Default")
      (node (ref "R6") (pin "2") (pinfunction "R2_2") (pintype "passive"))
      (node (ref "R9") (pin "1") (pinfunction "R1_1") (pintype "passive"))
      (node (ref "U4") (pin "2") (pinfunction "INA-_2") (pintype "input"))
    )
    (net (code "56") (name "Net-(R11-R1)") (class "Default")
      (node (ref "R11") (pin "1") (pinfunction "R1_1") (pintype "passive"))
      (node (ref "R7") (pin "2") (pinfunction "R2_2") (pintype "passive"))
      (node (ref "U5") (pin "2") (pinfunction "INA-_2") (pintype "input"))
    )
    (net (code "57") (name "Net-(R15-R1)") (class "Default")
      (node (ref "R15") (pin "1") (pinfunction "R1_1") (pintype "passive"))
      (node (ref "R30") (pin "1") (pinfunction "R1_1") (pintype "passive"))
      (node (ref "U4") (pin "3") (pinfunction "INA+_3") (pintype "input"))
    )
    (net (code "58") (name "Net-(R17-R1)") (class "Default")
      (node (ref "R17") (pin "1") (pinfunction "R1_1") (pintype "passive"))
      (node (ref "R32") (pin "1") (pinfunction "R1_1") (pintype "passive"))
      (node (ref "U5") (pin "3") (pinfunction "INA+_3") (pintype "input"))
    )
    (net (code "59") (name "Net-(R18-R2)") (class "Default")
      (node (ref "R18") (pin "2") (pinfunction "R2_2") (pintype "passive"))
      (node (ref "R21") (pin "1") (pinfunction "R1_1") (pintype "passive"))
      (node (ref "U4") (pin "6") (pinfunction "INB-_6") (pintype "input"))
    )
    (net (code "60") (name "Net-(R19-R2)") (class "Default")
      (node (ref "R19") (pin "2") (pinfunction "R2_2") (pintype "passive"))
      (node (ref "R23") (pin "1") (pinfunction "R1_1") (pintype "passive"))
      (node (ref "U5") (pin "6") (pinfunction "INB-_6") (pintype "input"))
    )
    (net (code "61") (name "Net-(R27-R1)") (class "Default")
      (node (ref "R27") (pin "1") (pinfunction "R1_1") (pintype "passive"))
      (node (ref "R31") (pin "1") (pinfunction "R1_1") (pintype "passive"))
      (node (ref "U4") (pin "5") (pinfunction "INB+_5") (pintype "input"))
    )
    (net (code "62") (name "Net-(R29-R1)") (class "Default")
      (node (ref "R29") (pin "1") (pinfunction "R1_1") (pintype "passive"))
      (node (ref "R33") (pin "1") (pinfunction "R1_1") (pintype "passive"))
      (node (ref "U5") (pin "5") (pinfunction "INB+_5") (pintype "input"))
    )
    (net (code "63") (name "Net-(R34-R2)") (class "Default")
      (node (ref "R34") (pin "2") (pinfunction "R2_2") (pintype "passive"))
      (node (ref "R36") (pin "1") (pinfunction "R1_1") (pintype "passive"))
      (node (ref "U6") (pin "2") (pinfunction "INA-_2") (pintype "input"))
    )
    (net (code "64") (name "Net-(R37-R2)") (class "Default")
      (node (ref "R37") (pin "2") (pinfunction "R2_2") (pintype "passive"))
      (node (ref "R40") (pin "1") (pinfunction "R1_1") (pintype "passive"))
      (node (ref "U7") (pin "2") (pinfunction "INA-_2") (pintype "input"))
    )
    (net (code "65") (name "Net-(R42-R1)") (class "Default")
      (node (ref "R42") (pin "1") (pinfunction "R1_1") (pintype "passive"))
      (node (ref "R58") (pin "1") (pinfunction "R1_1") (pintype "passive"))
      (node (ref "U6") (pin "3") (pinfunction "INA+_3") (pintype "input"))
    )
    (net (code "66") (name "Net-(R44-R2)") (class "Default")
      (node (ref "R44") (pin "2") (pinfunction "R2_2") (pintype "passive"))
      (node (ref "R48") (pin "1") (pinfunction "R1_1") (pintype "passive"))
      (node (ref "U6") (pin "6") (pinfunction "INB-_6") (pintype "input"))
    )
    (net (code "67") (name "Net-(R46-R1)") (class "Default")
      (node (ref "R46") (pin "1") (pinfunction "R1_1") (pintype "passive"))
      (node (ref "R60") (pin "1") (pinfunction "R1_1") (pintype "passive"))
      (node (ref "U7") (pin "3") (pinfunction "INA+_3") (pintype "input"))
    )
    (net (code "68") (name "Net-(R49-R2)") (class "Default")
      (node (ref "R49") (pin "2") (pinfunction "R2_2") (pintype "passive"))
      (node (ref "R52") (pin "1") (pinfunction "R1_1") (pintype "passive"))
      (node (ref "U7") (pin "6") (pinfunction "INB-_6") (pintype "input"))
    )
    (net (code "69") (name "Net-(R54-R1)") (class "Default")
      (node (ref "R54") (pin "1") (pinfunction "R1_1") (pintype "passive"))
      (node (ref "R59") (pin "1") (pinfunction "R1_1") (pintype "passive"))
      (node (ref "U6") (pin "5") (pinfunction "INB+_5") (pintype "input"))
    )
    (net (code "70") (name "Net-(R57-R1)") (class "Default")
      (node (ref "R57") (pin "1") (pinfunction "R1_1") (pintype "passive"))
      (node (ref "R61") (pin "1") (pinfunction "R1_1") (pintype "passive"))
      (node (ref "U7") (pin "5") (pinfunction "INB+_5") (pintype "input"))
    )
  )
)
